# Telex.net
KiCad netlist of a schematic drawn in EAGLE
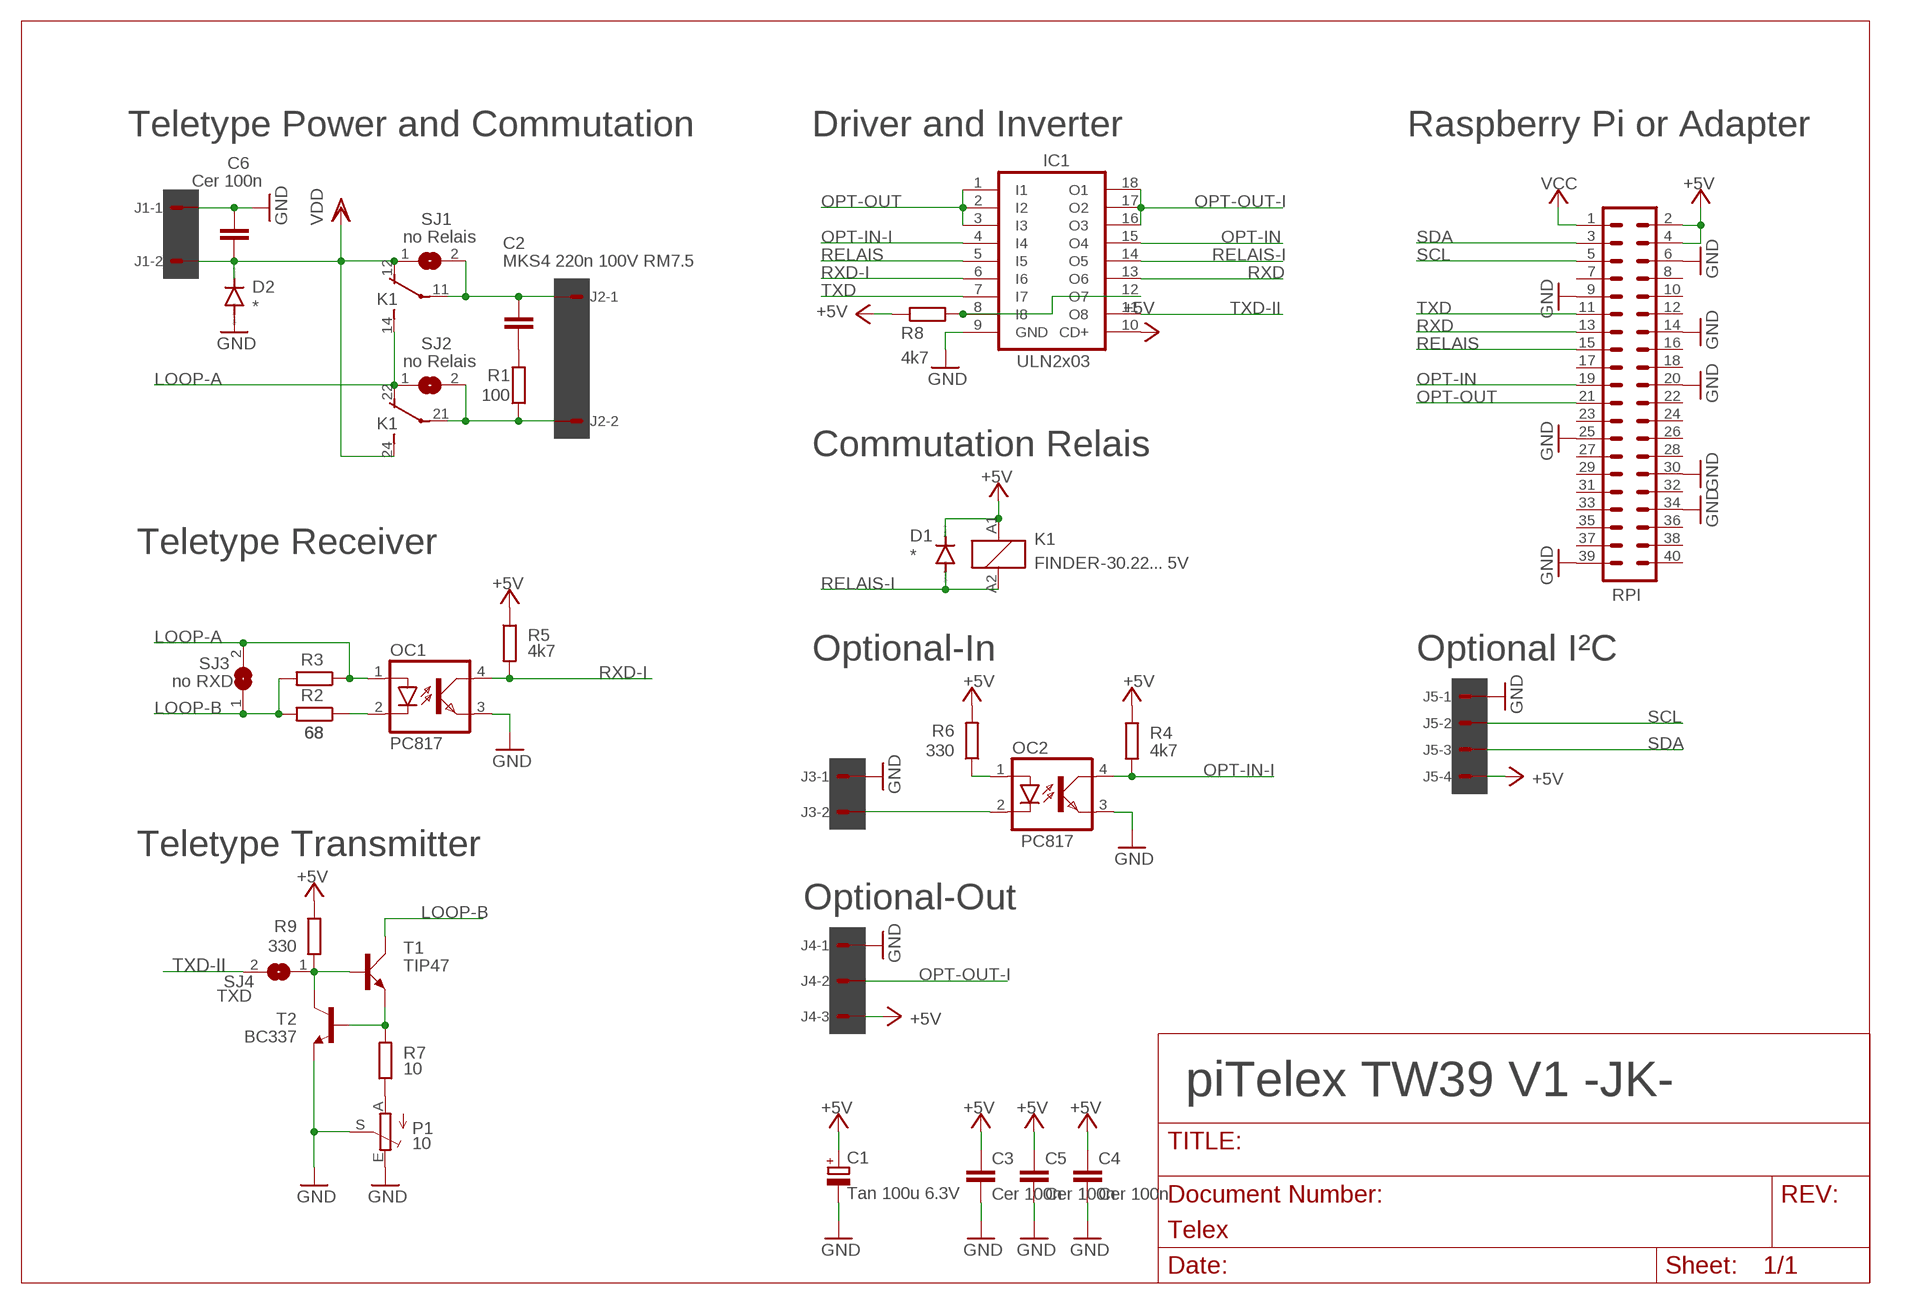
[diagram p0: schematic, sheet 1]

(export (version "E")
  (design (tool "Eeschema 10.0.6"))
  (components
    (comp (ref "C1")
      (value "Tan 100u 6.3V")
      (footprint "eagle-import:E2,5-6")
      (libsource (lib "eagle-import") (part "CPOL-EUE2.5-6"))
    )
    (comp (ref "C2")
      (value "MKS4 220n 100V RM7.5")
      (footprint "eagle-import:C075-042X103")
      (libsource (lib "eagle-import") (part "C-EU075-042X103"))
    )
    (comp (ref "C3")
      (value "Cer 100n")
      (footprint "eagle-import:C050-024X044")
      (libsource (lib "eagle-import") (part "C-EU050-024X044"))
    )
    (comp (ref "C4")
      (value "Cer 100n")
      (footprint "eagle-import:C050-024X044")
      (libsource (lib "eagle-import") (part "C-EU050-024X044"))
    )
    (comp (ref "C5")
      (value "Cer 100n")
      (footprint "eagle-import:C050-024X044")
      (libsource (lib "eagle-import") (part "C-EU050-024X044"))
    )
    (comp (ref "C6")
      (value "Cer 100n")
      (footprint "eagle-import:C050-024X044")
      (libsource (lib "eagle-import") (part "C-EU050-024X044"))
    )
    (comp (ref "D1")
      (value "*")
      (footprint "eagle-import:MINIMELF")
      (libsource (lib "eagle-import") (part "DIODE-MINIMELF"))
    )
    (comp (ref "D2")
      (value "*")
      (footprint "eagle-import:MINIMELF")
      (libsource (lib "eagle-import") (part "DIODE-MINIMELF"))
    )
    (comp (ref "IC1")
      (value "ULN2x03")
      (footprint "eagle-import:DIL18")
      (libsource (lib "eagle-import") (part "ULN2803A"))
    )
    (comp (ref "J1")
      (value "22-27-2021-02")
      (footprint "eagle-import:6410-02")
      (fields (field (name "MF") "MOLEX"))
      (libsource (lib "eagle-import") (part "22-?-0227-2021"))
    )
    (comp (ref "J2")
      (value "22-27-2021-02")
      (footprint "eagle-import:6410-02")
      (fields (field (name "MF") "MOLEX"))
      (libsource (lib "eagle-import") (part "22-?-0227-2021"))
    )
    (comp (ref "J3")
      (value "22-27-2021-02")
      (footprint "eagle-import:6410-02")
      (fields (field (name "MF") "MOLEX"))
      (libsource (lib "eagle-import") (part "22-?-0227-2021"))
    )
    (comp (ref "J4")
      (value "22-27-2031-03")
      (footprint "eagle-import:6410-03")
      (fields (field (name "MF") "MOLEX"))
      (libsource (lib "eagle-import") (part "22-?-0327-2031"))
    )
    (comp (ref "J5")
      (value "22-27-2041-04")
      (footprint "eagle-import:6410-04")
      (fields (field (name "MF") "MOLEX"))
      (libsource (lib "eagle-import") (part "22-?-0427-2041"))
    )
    (comp (ref "K1")
      (value "FINDER-30.22... 5V")
      (footprint "eagle-import:FINDER-30.22")
      (libsource (lib "eagle-import") (part "FINDER-30.22"))
    )
    (comp (ref "OC1")
      (value "PC817")
      (footprint "eagle-import:DIL04")
      (fields (field (name "MPN") "PC817X4J000F"))
      (libsource (lib "eagle-import") (part "PC817"))
    )
    (comp (ref "OC2")
      (value "PC817")
      (footprint "eagle-import:DIL04")
      (fields (field (name "MPN") "PC817X4J000F"))
      (libsource (lib "eagle-import") (part "PC817"))
    )
    (comp (ref "P1")
      (value "10")
      (footprint "eagle-import:S64Y")
      (libsource (lib "eagle-import") (part "TRIM_EU-S64Y"))
    )
    (comp (ref "R1")
      (value "100")
      (footprint "eagle-import:0204_7")
      (libsource (lib "eagle-import") (part "R-EU_0204/7"))
    )
    (comp (ref "R2")
      (value "68")
      (footprint "eagle-import:0204_7")
      (libsource (lib "eagle-import") (part "R-EU_0204/7"))
    )
    (comp (ref "R3")
      (value "68")
      (footprint "eagle-import:0204_7")
      (libsource (lib "eagle-import") (part "R-EU_0204/7"))
    )
    (comp (ref "R4")
      (value "4k7")
      (footprint "eagle-import:0204_7")
      (libsource (lib "eagle-import") (part "R-EU_0204/7"))
    )
    (comp (ref "R5")
      (value "4k7")
      (footprint "eagle-import:0204_7")
      (libsource (lib "eagle-import") (part "R-EU_0204/7"))
    )
    (comp (ref "R6")
      (value "330")
      (footprint "eagle-import:0204_7")
      (libsource (lib "eagle-import") (part "R-EU_0204/7"))
    )
    (comp (ref "R7")
      (value "10")
      (footprint "eagle-import:0204_7")
      (libsource (lib "eagle-import") (part "R-EU_0204/7"))
    )
    (comp (ref "R8")
      (value "4k7")
      (footprint "eagle-import:0204_7")
      (libsource (lib "eagle-import") (part "R-EU_0204/7"))
    )
    (comp (ref "R9")
      (value "330")
      (footprint "eagle-import:0204_7")
      (libsource (lib "eagle-import") (part "R-EU_0204/7"))
    )
    (comp (ref "RPI")
      (value "MA20-2")
      (footprint "eagle-import:MA20-2")
      (libsource (lib "eagle-import") (part "MA20-2"))
    )
    (comp (ref "SJ1")
      (value "no Relais")
      (footprint "eagle-import:SJ")
      (libsource (lib "eagle-import") (part "SJ"))
    )
    (comp (ref "SJ2")
      (value "no Relais")
      (footprint "eagle-import:SJ")
      (libsource (lib "eagle-import") (part "SJ"))
    )
    (comp (ref "SJ3")
      (value "no RXD")
      (footprint "eagle-import:SJ")
      (libsource (lib "eagle-import") (part "SJ"))
    )
    (comp (ref "SJ4")
      (value "TXD")
      (footprint "eagle-import:SJ")
      (libsource (lib "eagle-import") (part "SJ"))
    )
    (comp (ref "T1")
      (value "TIP47")
      (footprint "eagle-import:TO220AV")
      (libsource (lib "eagle-import") (part "TIP41C"))
    )
    (comp (ref "T2")
      (value "BC337")
      (footprint "eagle-import:TO92")
      (libsource (lib "eagle-import") (part "BC337"))
    )
  )
  (nets
    (net (code "1") (name "+5V") (class "Default")
      (node (ref "C1") (pin "+") (pinfunction "+_+") (pintype "passive"))
      (node (ref "C3") (pin "1") (pinfunction "1_1") (pintype "passive"))
      (node (ref "C4") (pin "1") (pinfunction "1_1") (pintype "passive"))
      (node (ref "C5") (pin "1") (pinfunction "1_1") (pintype "passive"))
      (node (ref "D1") (pin "C") (pinfunction "C_C") (pintype "passive"))
      (node (ref "IC1") (pin "10") (pinfunction "CD+_10") (pintype "passive"))
      (node (ref "J4") (pin "3") (pinfunction "S_3") (pintype "passive"))
      (node (ref "J5") (pin "4") (pinfunction "S_4") (pintype "passive"))
      (node (ref "K1") (pin "A1") (pinfunction "1_A1") (pintype "passive"))
      (node (ref "R4") (pin "1") (pinfunction "1_1") (pintype "passive"))
      (node (ref "R5") (pin "1") (pinfunction "1_1") (pintype "passive"))
      (node (ref "R6") (pin "2") (pinfunction "2_2") (pintype "passive"))
      (node (ref "R8") (pin "1") (pinfunction "1_1") (pintype "passive"))
      (node (ref "R9") (pin "1") (pinfunction "1_1") (pintype "passive"))
      (node (ref "RPI") (pin "2") (pinfunction "2_2") (pintype "passive"))
      (node (ref "RPI") (pin "4") (pinfunction "4_4") (pintype "passive"))
    )
    (net (code "2") (name "/LOOP-A") (class "Default")
      (node (ref "K1") (pin "14") (pinfunction "S_14") (pintype "passive"))
      (node (ref "K1") (pin "22") (pinfunction "O_22") (pintype "passive"))
      (node (ref "OC1") (pin "1") (pinfunction "A_1") (pintype "passive"))
      (node (ref "R3") (pin "1") (pinfunction "1_1") (pintype "passive"))
      (node (ref "SJ2") (pin "1") (pinfunction "1_1") (pintype "passive"))
      (node (ref "SJ3") (pin "2") (pinfunction "2_2") (pintype "passive"))
    )
    (net (code "3") (name "/LOOP-B") (class "Default")
      (node (ref "R2") (pin "2") (pinfunction "2_2") (pintype "passive"))
      (node (ref "R3") (pin "2") (pinfunction "2_2") (pintype "passive"))
      (node (ref "SJ3") (pin "1") (pinfunction "1_1") (pintype "passive"))
      (node (ref "T1") (pin "C") (pinfunction "C_C") (pintype "passive"))
    )
    (net (code "4") (name "/OPT-IN") (class "Default")
      (node (ref "IC1") (pin "15") (pinfunction "O4_15") (pintype "open_collector"))
      (node (ref "RPI") (pin "19") (pinfunction "19_19") (pintype "passive"))
    )
    (net (code "5") (name "/OPT-IN-I") (class "Default")
      (node (ref "IC1") (pin "4") (pinfunction "I4_4") (pintype "input"))
      (node (ref "OC2") (pin "4") (pinfunction "COL_4") (pintype "passive"))
      (node (ref "R4") (pin "2") (pinfunction "2_2") (pintype "passive"))
    )
    (net (code "6") (name "/OPT-OUT") (class "Default")
      (node (ref "IC1") (pin "1") (pinfunction "I1_1") (pintype "input"))
      (node (ref "IC1") (pin "2") (pinfunction "I2_2") (pintype "input"))
      (node (ref "IC1") (pin "3") (pinfunction "I3_3") (pintype "input"))
      (node (ref "RPI") (pin "21") (pinfunction "21_21") (pintype "passive"))
    )
    (net (code "7") (name "/OPT-OUT-I") (class "Default")
      (node (ref "IC1") (pin "16") (pinfunction "O3_16") (pintype "open_collector"))
      (node (ref "IC1") (pin "17") (pinfunction "O2_17") (pintype "open_collector"))
      (node (ref "IC1") (pin "18") (pinfunction "O1_18") (pintype "open_collector"))
      (node (ref "J4") (pin "2") (pinfunction "S_2") (pintype "passive"))
    )
    (net (code "8") (name "/RELAIS") (class "Default")
      (node (ref "IC1") (pin "5") (pinfunction "I5_5") (pintype "input"))
      (node (ref "RPI") (pin "15") (pinfunction "15_15") (pintype "passive"))
    )
    (net (code "9") (name "/RELAIS-I") (class "Default")
      (node (ref "D1") (pin "A") (pinfunction "A_A") (pintype "passive"))
      (node (ref "IC1") (pin "14") (pinfunction "O5_14") (pintype "open_collector"))
      (node (ref "K1") (pin "A2") (pinfunction "2_A2") (pintype "passive"))
    )
    (net (code "10") (name "/RXD") (class "Default")
      (node (ref "IC1") (pin "13") (pinfunction "O6_13") (pintype "open_collector"))
      (node (ref "RPI") (pin "13") (pinfunction "13_13") (pintype "passive"))
    )
    (net (code "11") (name "/RXD-I") (class "Default")
      (node (ref "IC1") (pin "6") (pinfunction "I6_6") (pintype "input"))
      (node (ref "OC1") (pin "4") (pinfunction "COL_4") (pintype "passive"))
      (node (ref "R5") (pin "2") (pinfunction "2_2") (pintype "passive"))
    )
    (net (code "12") (name "/SCL") (class "Default")
      (node (ref "J5") (pin "2") (pinfunction "S_2") (pintype "passive"))
      (node (ref "RPI") (pin "5") (pinfunction "5_5") (pintype "passive"))
    )
    (net (code "13") (name "/SDA") (class "Default")
      (node (ref "J5") (pin "3") (pinfunction "S_3") (pintype "passive"))
      (node (ref "RPI") (pin "3") (pinfunction "3_3") (pintype "passive"))
    )
    (net (code "14") (name "/TXD") (class "Default")
      (node (ref "IC1") (pin "7") (pinfunction "I7_7") (pintype "input"))
      (node (ref "RPI") (pin "11") (pinfunction "11_11") (pintype "passive"))
    )
    (net (code "15") (name "/TXD-II") (class "Default")
      (node (ref "IC1") (pin "11") (pinfunction "O8_11") (pintype "open_collector"))
      (node (ref "SJ4") (pin "2") (pinfunction "2_2") (pintype "passive"))
    )
    (net (code "16") (name "GND") (class "Default")
      (node (ref "C1") (pin "-") (pinfunction "-_-") (pintype "passive"))
      (node (ref "C3") (pin "2") (pinfunction "2_2") (pintype "passive"))
      (node (ref "C4") (pin "2") (pinfunction "2_2") (pintype "passive"))
      (node (ref "C5") (pin "2") (pinfunction "2_2") (pintype "passive"))
      (node (ref "C6") (pin "2") (pinfunction "2_2") (pintype "passive"))
      (node (ref "D2") (pin "A") (pinfunction "A_A") (pintype "passive"))
      (node (ref "IC1") (pin "9") (pinfunction "GND_9") (pintype "power_in"))
      (node (ref "J1") (pin "1") (pinfunction "S_1") (pintype "passive"))
      (node (ref "J3") (pin "1") (pinfunction "S_1") (pintype "passive"))
      (node (ref "J4") (pin "1") (pinfunction "S_1") (pintype "passive"))
      (node (ref "J5") (pin "1") (pinfunction "S_1") (pintype "passive"))
      (node (ref "OC1") (pin "3") (pinfunction "EMIT_3") (pintype "passive"))
      (node (ref "OC2") (pin "3") (pinfunction "EMIT_3") (pintype "passive"))
      (node (ref "P1") (pin "E") (pinfunction "E_E") (pintype "passive"))
      (node (ref "P1") (pin "S") (pinfunction "S_S") (pintype "passive"))
      (node (ref "RPI") (pin "14") (pinfunction "14_14") (pintype "passive"))
      (node (ref "RPI") (pin "20") (pinfunction "20_20") (pintype "passive"))
      (node (ref "RPI") (pin "25") (pinfunction "25_25") (pintype "passive"))
      (node (ref "RPI") (pin "30") (pinfunction "30_30") (pintype "passive"))
      (node (ref "RPI") (pin "34") (pinfunction "34_34") (pintype "passive"))
      (node (ref "RPI") (pin "39") (pinfunction "39_39") (pintype "passive"))
      (node (ref "RPI") (pin "6") (pinfunction "6_6") (pintype "passive"))
      (node (ref "RPI") (pin "9") (pinfunction "9_9") (pintype "passive"))
      (node (ref "T2") (pin "1") (pinfunction "E_1") (pintype "passive"))
    )
    (net (code "17") (name "Net-(C2-Pad2)") (class "Default")
      (node (ref "C2") (pin "2") (pinfunction "2_2") (pintype "passive"))
      (node (ref "R1") (pin "2") (pinfunction "2_2") (pintype "passive"))
    )
    (net (code "18") (name "Net-(IC1-I8)") (class "Default")
      (node (ref "IC1") (pin "12") (pinfunction "O7_12") (pintype "open_collector"))
      (node (ref "IC1") (pin "8") (pinfunction "I8_8") (pintype "input"))
      (node (ref "R8") (pin "2") (pinfunction "2_2") (pintype "passive"))
    )
    (net (code "19") (name "Net-(J2A-S)") (class "Default")
      (node (ref "C2") (pin "1") (pinfunction "1_1") (pintype "passive"))
      (node (ref "J2") (pin "1") (pinfunction "S_1") (pintype "passive"))
      (node (ref "K1") (pin "11") (pinfunction "P_11") (pintype "passive"))
      (node (ref "SJ1") (pin "2") (pinfunction "2_2") (pintype "passive"))
    )
    (net (code "20") (name "Net-(J2B-S)") (class "Default")
      (node (ref "J2") (pin "2") (pinfunction "S_2") (pintype "passive"))
      (node (ref "K1") (pin "21") (pinfunction "P_21") (pintype "passive"))
      (node (ref "R1") (pin "1") (pinfunction "1_1") (pintype "passive"))
      (node (ref "SJ2") (pin "2") (pinfunction "2_2") (pintype "passive"))
    )
    (net (code "21") (name "Net-(J3B-S)") (class "Default")
      (node (ref "J3") (pin "2") (pinfunction "S_2") (pintype "passive"))
      (node (ref "OC2") (pin "2") (pinfunction "C_2") (pintype "passive"))
    )
    (net (code "22") (name "Net-(OC1-C)") (class "Default")
      (node (ref "OC1") (pin "2") (pinfunction "C_2") (pintype "passive"))
      (node (ref "R2") (pin "1") (pinfunction "1_1") (pintype "passive"))
    )
    (net (code "23") (name "Net-(OC2-A)") (class "Default")
      (node (ref "OC2") (pin "1") (pinfunction "A_1") (pintype "passive"))
      (node (ref "R6") (pin "1") (pinfunction "1_1") (pintype "passive"))
    )
    (net (code "24") (name "Net-(P1-PadA)") (class "Default")
      (node (ref "P1") (pin "A") (pinfunction "A_A") (pintype "passive"))
      (node (ref "R7") (pin "1") (pinfunction "1_1") (pintype "passive"))
    )
    (net (code "25") (name "Net-(T2-B)") (class "Default")
      (node (ref "R7") (pin "2") (pinfunction "2_2") (pintype "passive"))
      (node (ref "T1") (pin "E") (pinfunction "E_E") (pintype "passive"))
      (node (ref "T2") (pin "2") (pinfunction "B_2") (pintype "passive"))
    )
    (net (code "26") (name "Net-(T2-C)") (class "Default")
      (node (ref "R9") (pin "2") (pinfunction "2_2") (pintype "passive"))
      (node (ref "SJ4") (pin "1") (pinfunction "1_1") (pintype "passive"))
      (node (ref "T1") (pin "B") (pinfunction "B_B") (pintype "passive"))
      (node (ref "T2") (pin "3") (pinfunction "C_3") (pintype "passive"))
    )
    (net (code "27") (name "VCC") (class "Default")
      (node (ref "RPI") (pin "1") (pinfunction "1_1") (pintype "passive"))
    )
    (net (code "28") (name "VDD") (class "Default")
      (node (ref "C6") (pin "1") (pinfunction "1_1") (pintype "passive"))
      (node (ref "D2") (pin "C") (pinfunction "C_C") (pintype "passive"))
      (node (ref "J1") (pin "2") (pinfunction "S_2") (pintype "passive"))
      (node (ref "K1") (pin "12") (pinfunction "O_12") (pintype "passive"))
      (node (ref "K1") (pin "24") (pinfunction "S_24") (pintype "passive"))
      (node (ref "SJ1") (pin "1") (pinfunction "1_1") (pintype "passive"))
    )
    (net (code "29") (name "unconnected-(RPI-Pad7)") (class "Default")
      (node (ref "RPI") (pin "7") (pinfunction "7_7") (pintype "passive"))
    )
    (net (code "30") (name "unconnected-(RPI-Pad8)") (class "Default")
      (node (ref "RPI") (pin "8") (pinfunction "8_8") (pintype "passive"))
    )
    (net (code "31") (name "unconnected-(RPI-Pad10)") (class "Default")
      (node (ref "RPI") (pin "10") (pinfunction "10_10") (pintype "passive"))
    )
    (net (code "32") (name "unconnected-(RPI-Pad12)") (class "Default")
      (node (ref "RPI") (pin "12") (pinfunction "12_12") (pintype "passive"))
    )
    (net (code "33") (name "unconnected-(RPI-Pad16)") (class "Default")
      (node (ref "RPI") (pin "16") (pinfunction "16_16") (pintype "passive"))
    )
    (net (code "34") (name "unconnected-(RPI-Pad17)") (class "Default")
      (node (ref "RPI") (pin "17") (pinfunction "17_17") (pintype "passive"))
    )
    (net (code "35") (name "unconnected-(RPI-Pad18)") (class "Default")
      (node (ref "RPI") (pin "18") (pinfunction "18_18") (pintype "passive"))
    )
    (net (code "36") (name "unconnected-(RPI-Pad22)") (class "Default")
      (node (ref "RPI") (pin "22") (pinfunction "22_22") (pintype "passive"))
    )
    (net (code "37") (name "unconnected-(RPI-Pad23)") (class "Default")
      (node (ref "RPI") (pin "23") (pinfunction "23_23") (pintype "passive"))
    )
    (net (code "38") (name "unconnected-(RPI-Pad24)") (class "Default")
      (node (ref "RPI") (pin "24") (pinfunction "24_24") (pintype "passive"))
    )
    (net (code "39") (name "unconnected-(RPI-Pad26)") (class "Default")
      (node (ref "RPI") (pin "26") (pinfunction "26_26") (pintype "passive"))
    )
    (net (code "40") (name "unconnected-(RPI-Pad27)") (class "Default")
      (node (ref "RPI") (pin "27") (pinfunction "27_27") (pintype "passive"))
    )
    (net (code "41") (name "unconnected-(RPI-Pad28)") (class "Default")
      (node (ref "RPI") (pin "28") (pinfunction "28_28") (pintype "passive"))
    )
    (net (code "42") (name "unconnected-(RPI-Pad29)") (class "Default")
      (node (ref "RPI") (pin "29") (pinfunction "29_29") (pintype "passive"))
    )
    (net (code "43") (name "unconnected-(RPI-Pad31)") (class "Default")
      (node (ref "RPI") (pin "31") (pinfunction "31_31") (pintype "passive"))
    )
    (net (code "44") (name "unconnected-(RPI-Pad32)") (class "Default")
      (node (ref "RPI") (pin "32") (pinfunction "32_32") (pintype "passive"))
    )
    (net (code "45") (name "unconnected-(RPI-Pad33)") (class "Default")
      (node (ref "RPI") (pin "33") (pinfunction "33_33") (pintype "passive"))
    )
    (net (code "46") (name "unconnected-(RPI-Pad35)") (class "Default")
      (node (ref "RPI") (pin "35") (pinfunction "35_35") (pintype "passive"))
    )
    (net (code "47") (name "unconnected-(RPI-Pad36)") (class "Default")
      (node (ref "RPI") (pin "36") (pinfunction "36_36") (pintype "passive"))
    )
    (net (code "48") (name "unconnected-(RPI-Pad37)") (class "Default")
      (node (ref "RPI") (pin "37") (pinfunction "37_37") (pintype "passive"))
    )
    (net (code "49") (name "unconnected-(RPI-Pad38)") (class "Default")
      (node (ref "RPI") (pin "38") (pinfunction "38_38") (pintype "passive"))
    )
    (net (code "50") (name "unconnected-(RPI-Pad40)") (class "Default")
      (node (ref "RPI") (pin "40") (pinfunction "40_40") (pintype "passive"))
    )
  )
)
